# STM32H730_PINOUT.net
KiCad netlist of a schematic drawn in Altium Designer
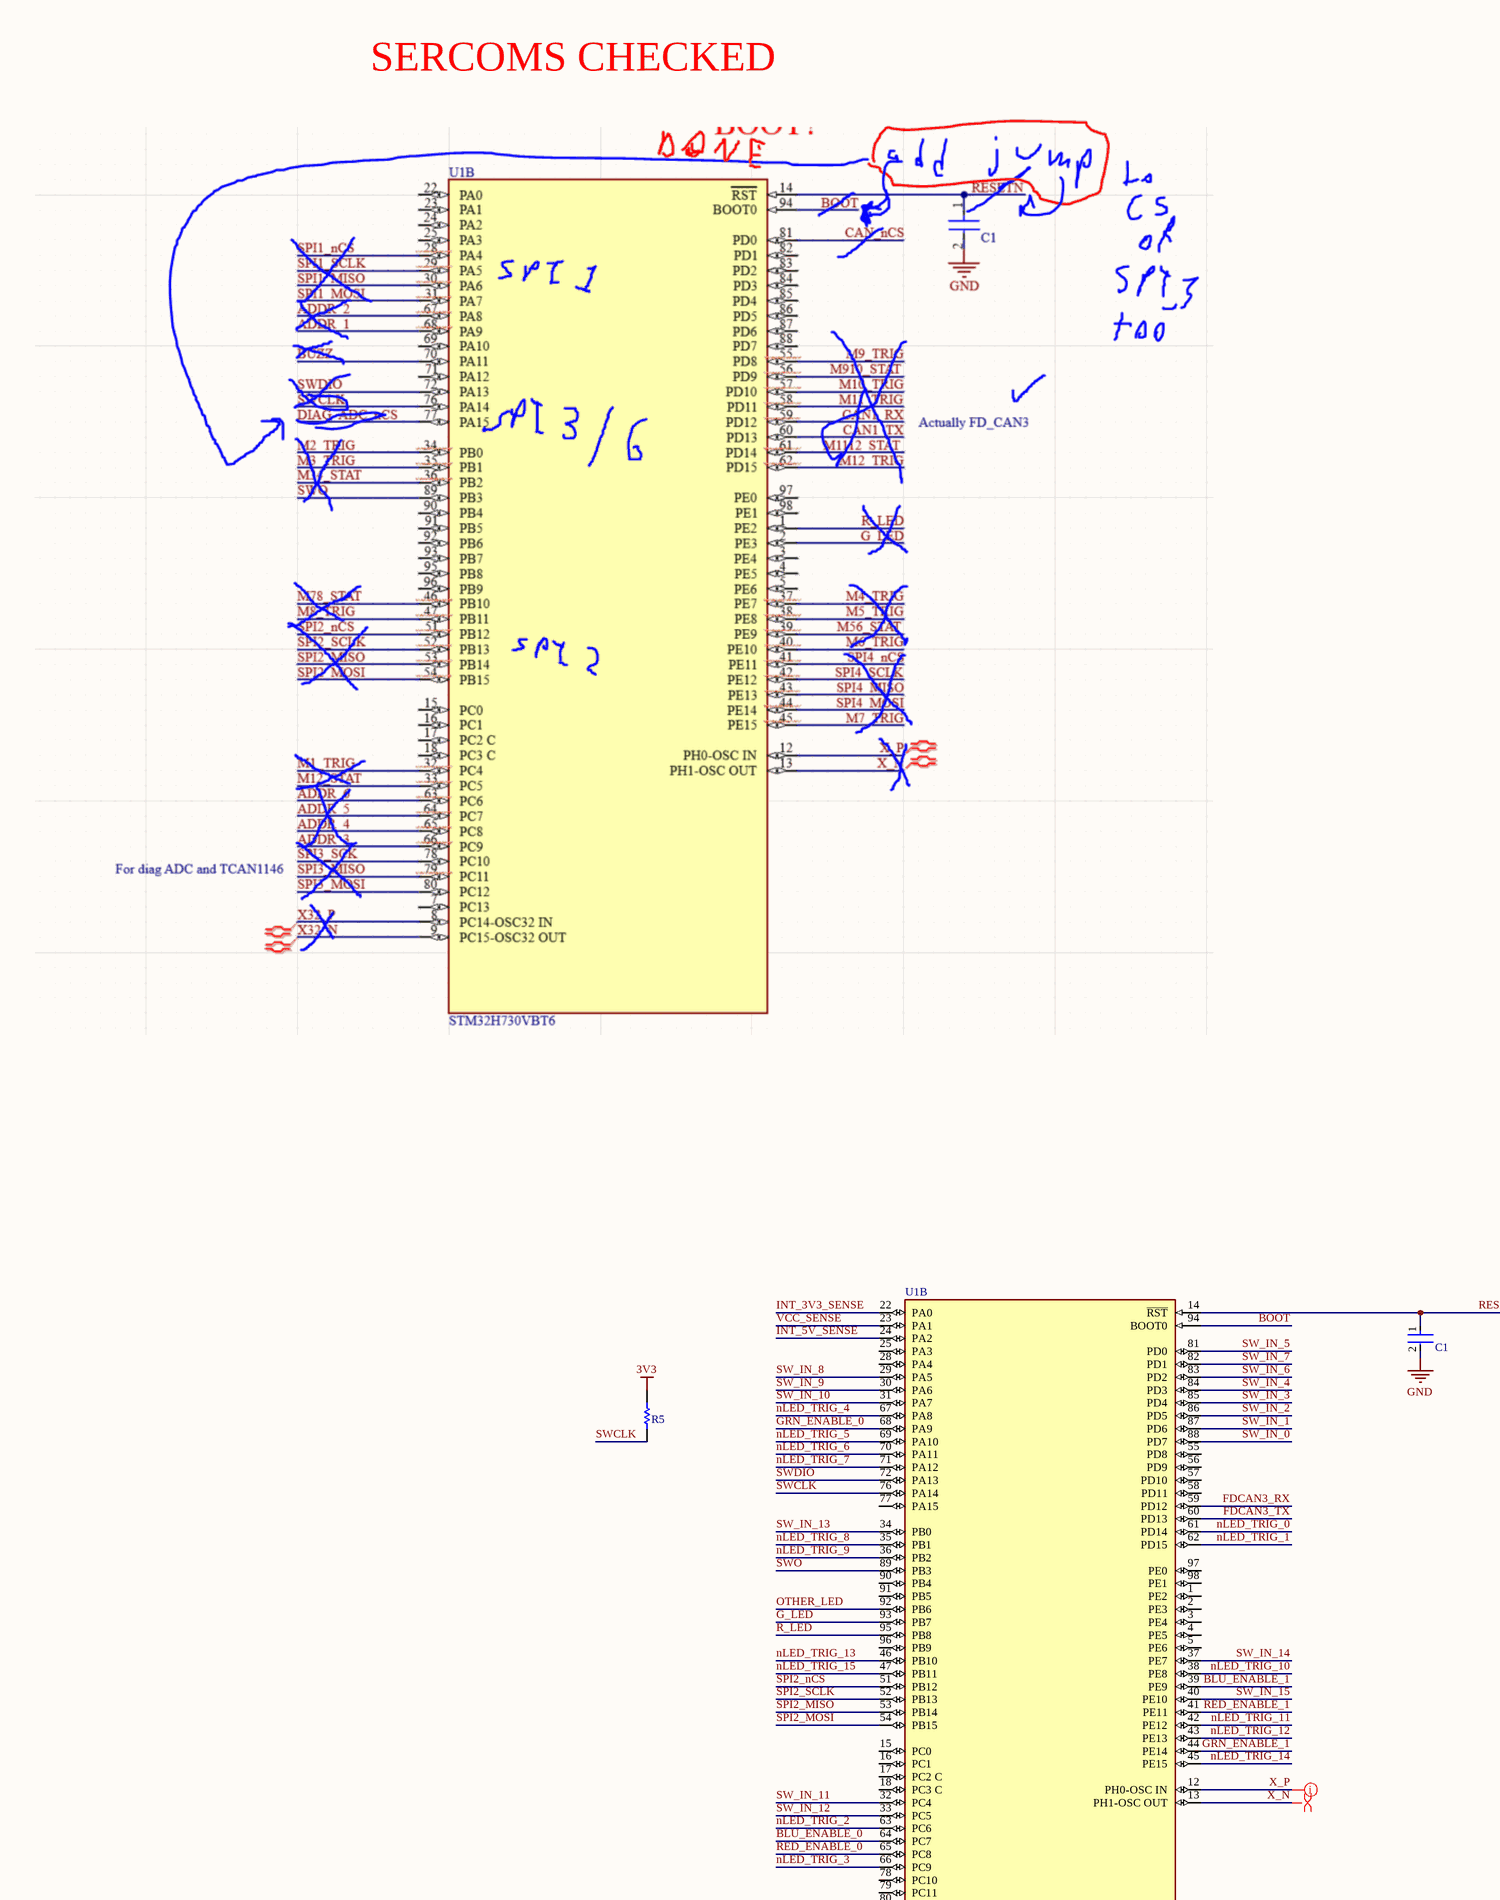
[diagram p0: STM32H730_PINOUT.SchDoc, top left]
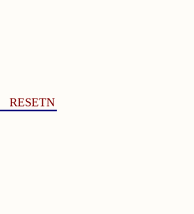
[diagram p1: STM32H730_PINOUT.SchDoc, top middle]
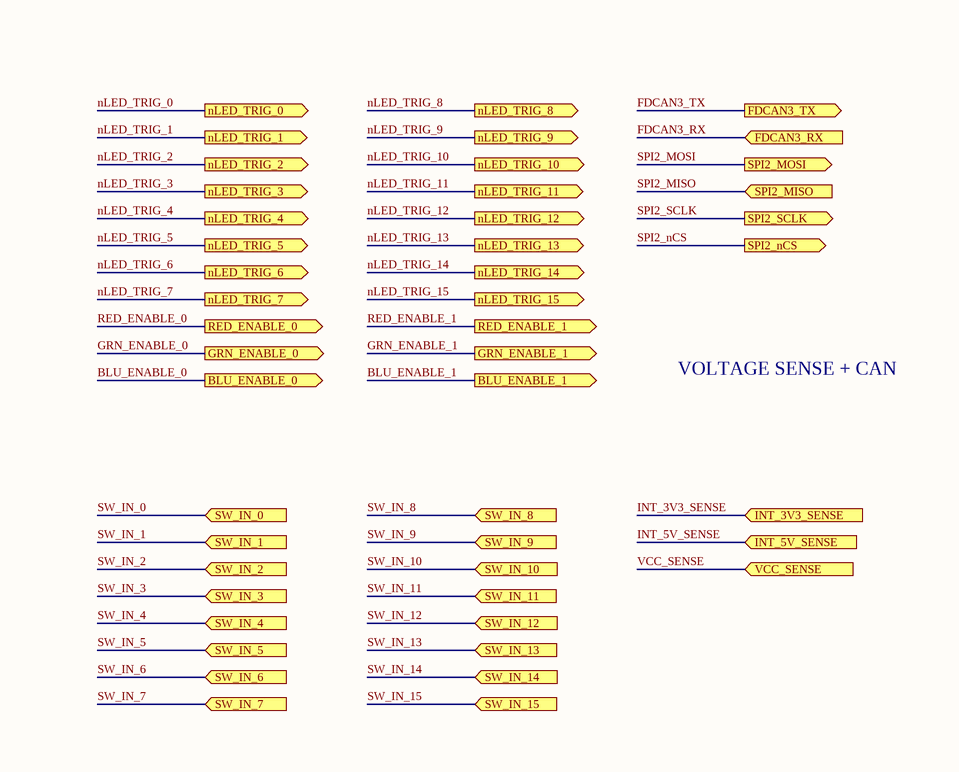
[diagram p2: STM32H730_PINOUT.SchDoc, top right]
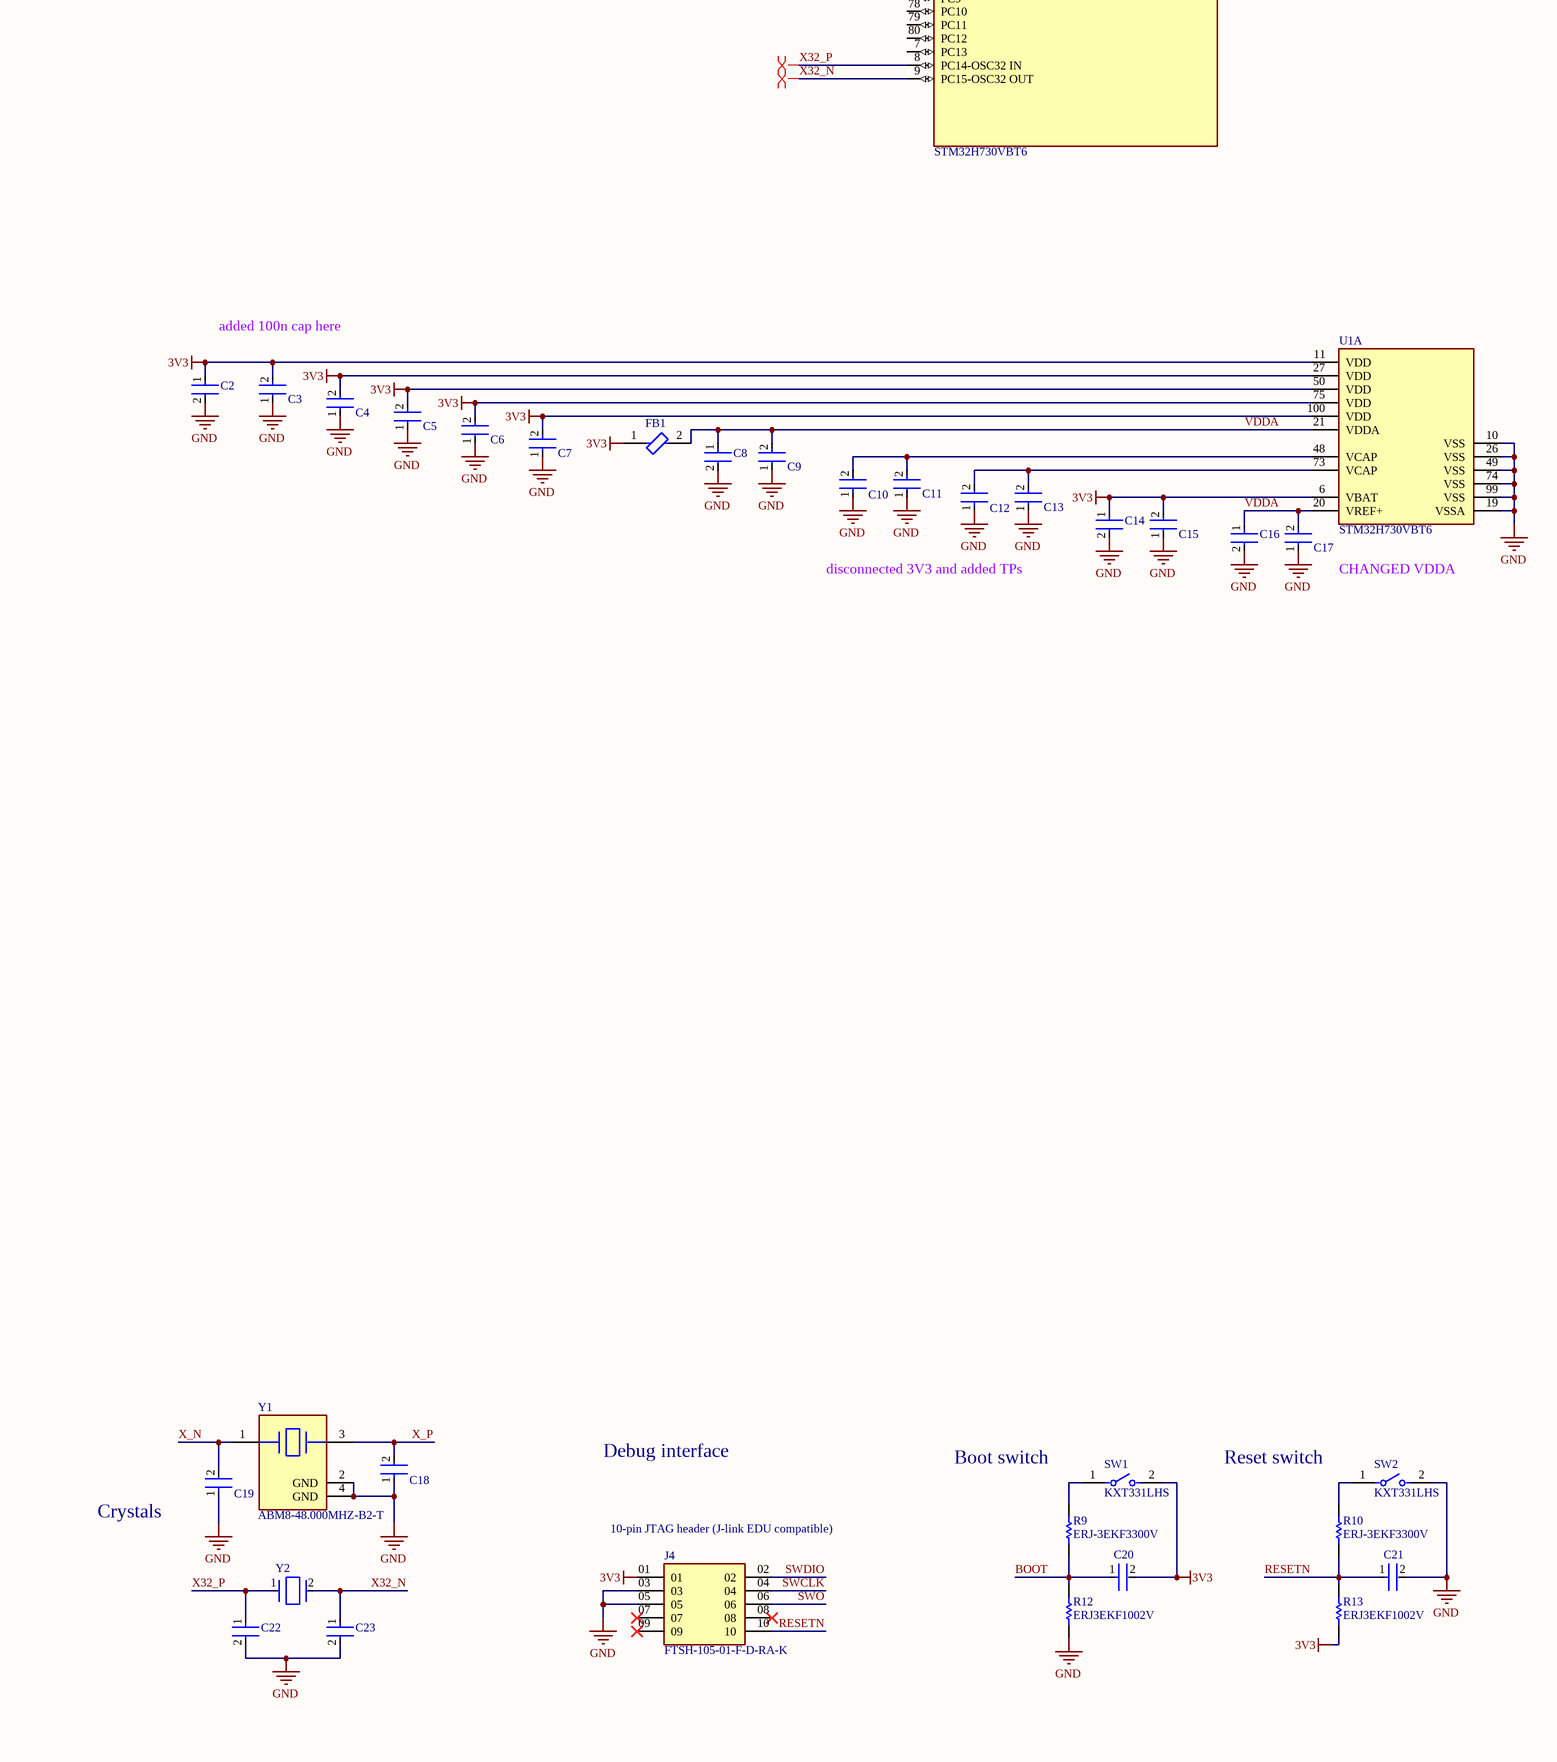
[diagram p3: STM32H730_PINOUT.SchDoc, bottom left]
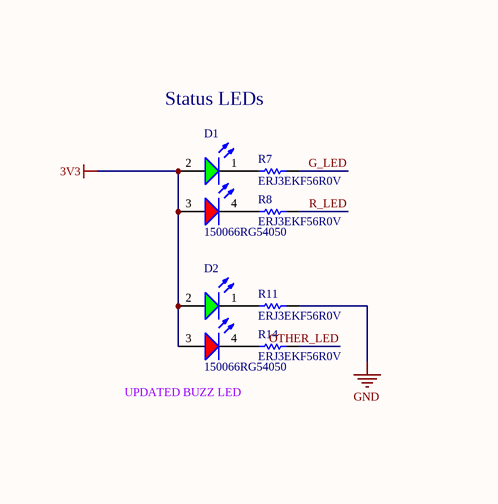
[diagram p4: STM32H730_PINOUT.SchDoc, bottom middle]
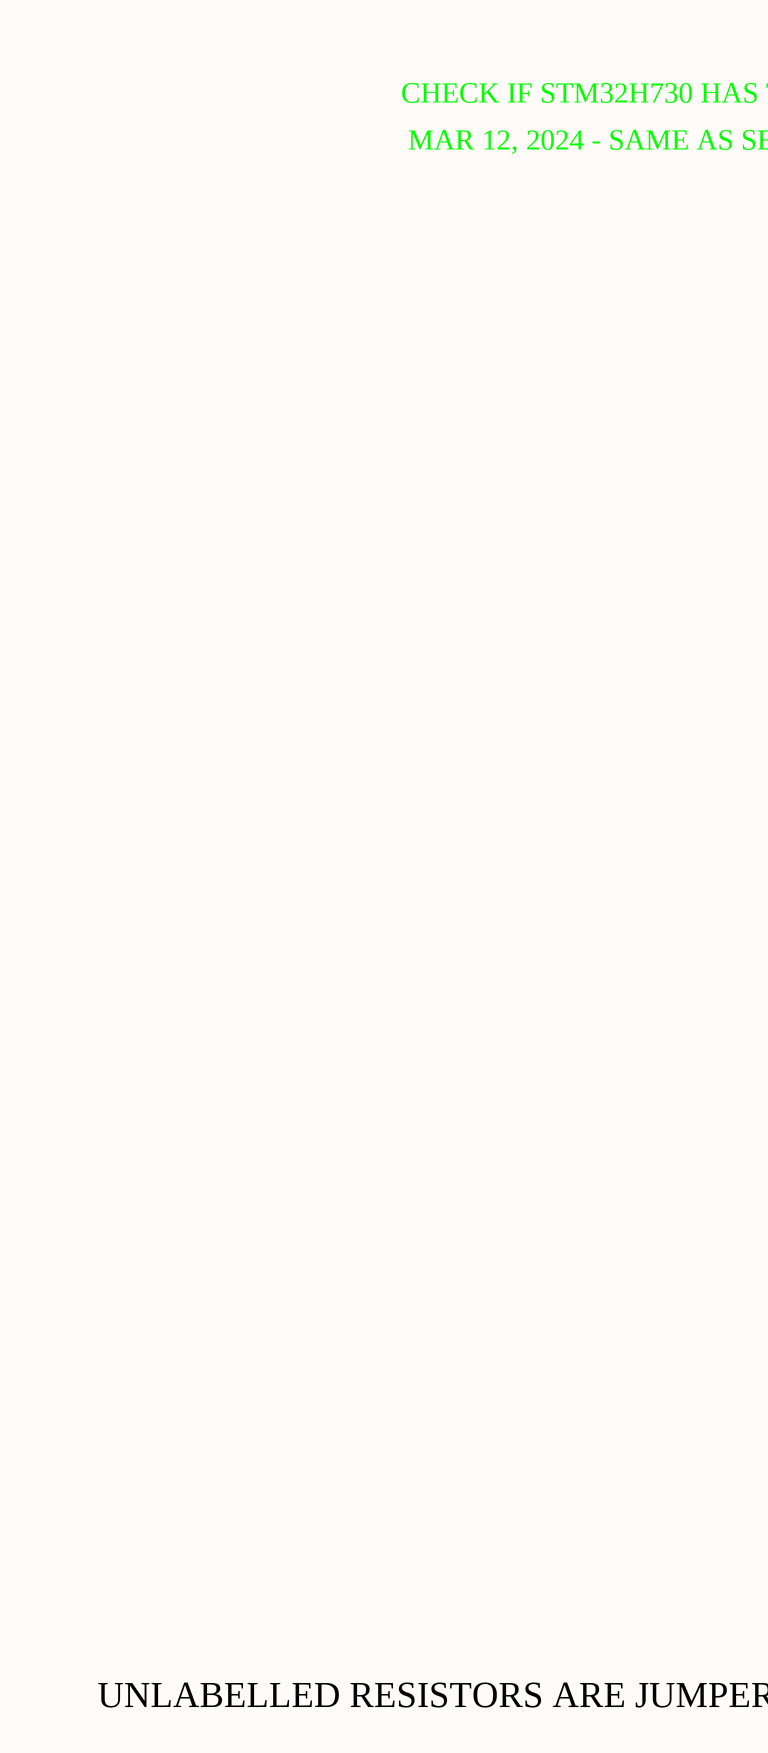
[diagram p5: STM32H730_PINOUT.SchDoc, bottom right]

(export (version "E")
  (design (tool "Eeschema 10.0.6"))
  (components
    (comp (ref "C1")
      (value "C0402C104K8PACTU")
      (footprint "FP-C0402-BB-MFG")
      (description "CAP CER 0.1UF 10V X5R 0402")
      (fields (field (name "MANUFACTURER") "Kemet") (field (name "TOLERANCE") "0.1"))
      (libsource (lib "Altium Content Vault") (part "b4654b650e69147ec39a6b967a45e02"))
    )
    (comp (ref "C2")
      (value "C1005X5R1A475K050BC")
      (footprint "FP-C1005-050-0_15-MFG")
      (description "CAP CER 4.7UF 10V X5R 0402")
      (fields (field (name "TOLERANCE") "10%"))
      (libsource (lib "Altium Content Vault") (part "b4654b650e69147ec39a6b967a45e02"))
    )
    (comp (ref "C3")
      (value "GRM155R71C104KA88D")
      (footprint "FP-GRM15-MFG")
      (description "CAP CER 0.1UF 16V X7R 0402")
      (fields
        (field (name "TOLERANCE") "10%")
        (field (name "OCTOPART") "https://octopart.com/grm155r71c104ka88d-murata-196880")
      )
      (libsource (lib "Altium Content Vault") (part "236180d848d6139a670b325ea6854c9"))
    )
    (comp (ref "C4")
      (value "GRM155R71C104KA88D")
      (footprint "FP-GRM15-MFG")
      (description "CAP CER 0.1UF 16V X7R 0402")
      (fields
        (field (name "TOLERANCE") "10%")
        (field (name "OCTOPART") "https://octopart.com/grm155r71c104ka88d-murata-196880")
      )
      (libsource (lib "Altium Content Vault") (part "236180d848d6139a670b325ea6854c9"))
    )
    (comp (ref "C5")
      (value "GRM155R71C104KA88D")
      (footprint "FP-GRM15-MFG")
      (description "CAP CER 0.1UF 16V X7R 0402")
      (fields
        (field (name "TOLERANCE") "10%")
        (field (name "OCTOPART") "https://octopart.com/grm155r71c104ka88d-murata-196880")
      )
      (libsource (lib "Altium Content Vault") (part "236180d848d6139a670b325ea6854c9"))
    )
    (comp (ref "C6")
      (value "GRM155R71C104KA88D")
      (footprint "FP-GRM15-MFG")
      (description "CAP CER 0.1UF 16V X7R 0402")
      (fields
        (field (name "TOLERANCE") "10%")
        (field (name "OCTOPART") "https://octopart.com/grm155r71c104ka88d-murata-196880")
      )
      (libsource (lib "Altium Content Vault") (part "236180d848d6139a670b325ea6854c9"))
    )
    (comp (ref "C7")
      (value "GRM155R71C104KA88D")
      (footprint "FP-GRM15-MFG")
      (description "CAP CER 0.1UF 16V X7R 0402")
      (fields
        (field (name "TOLERANCE") "10%")
        (field (name "OCTOPART") "https://octopart.com/grm155r71c104ka88d-murata-196880")
      )
      (libsource (lib "Altium Content Vault") (part "236180d848d6139a670b325ea6854c9"))
    )
    (comp (ref "C8")
      (value "EMK105BJ105KV-F")
      (footprint "FP-0402-L_1_0_0_05-W_0_5-IPC_A")
      (description "None")
      (fields (field (name "TOLERANCE") "10%"))
      (libsource (lib "Altium Content Vault") (part "b4654b650e69147ec39a6b967a45e02"))
    )
    (comp (ref "C9")
      (value "GRM155R71C104KA88D")
      (footprint "FP-GRM15-MFG")
      (description "CAP CER 0.1UF 16V X7R 0402")
      (fields
        (field (name "TOLERANCE") "10%")
        (field (name "OCTOPART") "https://octopart.com/grm155r71c104ka88d-murata-196880")
      )
      (libsource (lib "Altium Content Vault") (part "236180d848d6139a670b325ea6854c9"))
    )
    (comp (ref "C10")
      (value "C1005X7S1A225K050BC")
      (footprint "FP-C1005-050-0_15-0_1-MFG")
      (description "CAP CER 2.2UF 10V X7S 0402")
      (fields (field (name "TOLERANCE") "10%"))
      (libsource (lib "Altium Content Vault") (part "b4654b650e69147ec39a6b967a45e02"))
    )
    (comp (ref "C11")
      (value "GRM155R71C104KA88D")
      (footprint "FP-GRM15-MFG")
      (description "CAP CER 0.1UF 16V X7R 0402")
      (fields
        (field (name "TOLERANCE") "10%")
        (field (name "OCTOPART") "https://octopart.com/grm155r71c104ka88d-murata-196880")
      )
      (libsource (lib "Altium Content Vault") (part "236180d848d6139a670b325ea6854c9"))
    )
    (comp (ref "C12")
      (value "C1005X7S1A225K050BC")
      (footprint "FP-C1005-050-0_15-0_1-MFG")
      (description "CAP CER 2.2UF 10V X7S 0402")
      (fields (field (name "TOLERANCE") "10%"))
      (libsource (lib "Altium Content Vault") (part "b4654b650e69147ec39a6b967a45e02"))
    )
    (comp (ref "C13")
      (value "GRM155R71C104KA88D")
      (footprint "FP-GRM15-MFG")
      (description "CAP CER 0.1UF 16V X7R 0402")
      (fields
        (field (name "TOLERANCE") "10%")
        (field (name "OCTOPART") "https://octopart.com/grm155r71c104ka88d-murata-196880")
      )
      (libsource (lib "Altium Content Vault") (part "236180d848d6139a670b325ea6854c9"))
    )
    (comp (ref "C14")
      (value "EMK105BJ105KV-F")
      (footprint "FP-0402-L_1_0_0_05-W_0_5-IPC_A")
      (description "None")
      (fields (field (name "TOLERANCE") "10%"))
      (libsource (lib "Altium Content Vault") (part "b4654b650e69147ec39a6b967a45e02"))
    )
    (comp (ref "C15")
      (value "GRM155R71C104KA88D")
      (footprint "FP-GRM15-MFG")
      (description "CAP CER 0.1UF 16V X7R 0402")
      (fields
        (field (name "TOLERANCE") "10%")
        (field (name "OCTOPART") "https://octopart.com/grm155r71c104ka88d-murata-196880")
      )
      (libsource (lib "Altium Content Vault") (part "236180d848d6139a670b325ea6854c9"))
    )
    (comp (ref "C16")
      (value "EMK105BJ105KV-F")
      (footprint "FP-0402-L_1_0_0_05-W_0_5-IPC_A")
      (description "None")
      (fields (field (name "TOLERANCE") "10%"))
      (libsource (lib "Altium Content Vault") (part "b4654b650e69147ec39a6b967a45e02"))
    )
    (comp (ref "C17")
      (value "GRM155R71C104KA88D")
      (footprint "FP-GRM15-MFG")
      (description "CAP CER 0.1UF 16V X7R 0402")
      (fields
        (field (name "TOLERANCE") "10%")
        (field (name "OCTOPART") "https://octopart.com/grm155r71c104ka88d-murata-196880")
      )
      (libsource (lib "Altium Content Vault") (part "236180d848d6139a670b325ea6854c9"))
    )
    (comp (ref "C18")
      (value "08051A6R8CAT2A")
      (footprint "FP-0805-L_2_01_0_2-W_1_25-MFG")
      (description "General Purpose Ceramic Capacitor, 0805, 6.8pF, 0.25pF, C0G, 30ppm/°C, 100V")
      (fields (field (name "VOLTAGE") "100V") (field (name "TOLERANCE") "5%"))
      (libsource (lib "Altium Content Vault") (part "02cd4be3c70576c341d710602a673aa"))
    )
    (comp (ref "C19")
      (value "08051A6R8CAT2A")
      (footprint "FP-0805-L_2_01_0_2-W_1_25-MFG")
      (description "General Purpose Ceramic Capacitor, 0805, 6.8pF, 0.25pF, C0G, 30ppm/°C, 100V")
      (fields (field (name "VOLTAGE") "100V") (field (name "TOLERANCE") "5%"))
      (libsource (lib "Altium Content Vault") (part "02cd4be3c70576c341d710602a673aa"))
    )
    (comp (ref "C20")
      (value "C0402C104K8PACTU")
      (footprint "FP-C0402-BB-MFG")
      (description "CAP CER 0.1UF 10V X5R 0402")
      (fields (field (name "MANUFACTURER") "Kemet") (field (name "TOLERANCE") "0.1"))
      (libsource (lib "Altium Content Vault") (part "b4654b650e69147ec39a6b967a45e02"))
    )
    (comp (ref "C21")
      (value "C0402C104K8PACTU")
      (footprint "FP-C0402-BB-MFG")
      (description "CAP CER 0.1UF 10V X5R 0402")
      (fields (field (name "MANUFACTURER") "Kemet") (field (name "TOLERANCE") "0.1"))
      (libsource (lib "Altium Content Vault") (part "b4654b650e69147ec39a6b967a45e02"))
    )
    (comp (ref "C22")
      (value "04025A180FAT2A")
      (footprint "FP-0402-L_1_0_1-W_0_5_0_1-IPC_A")
      (description "General Purpose Ceramic Capacitor, 0402, 18pF, 1%, C0G, 30ppm/°C, 50V")
      (fields (field (name "TOLERANCE") "1%"))
      (libsource (lib "Altium Content Vault") (part "b4654b650e69147ec39a6b967a45e02"))
    )
    (comp (ref "C23")
      (value "04025A180FAT2A")
      (footprint "FP-0402-L_1_0_1-W_0_5_0_1-IPC_A")
      (description "General Purpose Ceramic Capacitor, 0402, 18pF, 1%, C0G, 30ppm/°C, 50V")
      (fields (field (name "TOLERANCE") "1%"))
      (libsource (lib "Altium Content Vault") (part "b4654b650e69147ec39a6b967a45e02"))
    )
    (comp (ref "D1")
      (value "150066RG54050")
      (footprint "WL-SBCD_0606")
      (description "Led, Red/Grn, 180Mcd/230Mcd, 624Nm/525Nm Rohs Compliant: Yes")
      (fields (field (name "SOURCE") "rgled.SchLib"))
      (libsource (lib "Space Concordia") (part "CMP-004-00034-2"))
    )
    (comp (ref "D2")
      (value "150066RG54050")
      (footprint "WL-SBCD_0606")
      (description "Led, Red/Grn, 180Mcd/230Mcd, 624Nm/525Nm Rohs Compliant: Yes")
      (fields (field (name "SOURCE") "rgled.SchLib"))
      (libsource (lib "Space Concordia") (part "CMP-004-00034-2"))
    )
    (comp (ref "FB1")
      (value "BLM15PX601SN1D")
      (footprint "FP-BLM15-0_05-MFG")
      (description "Chip Ferrite Bead, 0402, 600Ω @ 100MHz, 0.23Ω, 25%, 900mA")
      (fields (field (name "TOLERANCE") "25%"))
      (libsource (lib "Altium Content Vault") (part "5f30dd21d616792df468990f7003faa"))
    )
    (comp (ref "J4")
      (value "FTSH-105-01-F-D-RA-K")
      (footprint "FTSH-105-01-F-D-RA-K-Footprint-1")
      (libsource (lib "Space Concordia") (part "FTSH-105-01-F-D-RA-K-Symbol-1"))
    )
    (comp (ref "R5")
      (value "ERJ3EKF1002V")
      (footprint "RESC1609X55X30LL15T15")
      (description "Chip Resistor, 10 KOhm, +/- 1%, 0.1 W, -55 to 155 degC, 0603 (1608 Metric), RoHS, Tape and Reel")
      (fields (field (name "TOLERANCE") "1%") (field (name "MANUFACTURER") "Panasonic"))
      (libsource (lib "Altium Content Vault") (part "RES-2"))
    )
    (comp (ref "R7")
      (value "ERJ3EKF56R0V")
      (footprint "RESC1608X55X30NL15T15")
      (fields (field (name "MANUFACTURER") "Panasonic"))
      (libsource (lib "Altium Content Vault") (part "RES"))
    )
    (comp (ref "R8")
      (value "ERJ3EKF56R0V")
      (footprint "RESC1608X55X30NL15T15")
      (fields (field (name "MANUFACTURER") "Panasonic"))
      (libsource (lib "Altium Content Vault") (part "RES"))
    )
    (comp (ref "R9")
      (value "ERJ-3EKF3300V")
      (footprint "RESC1608X55X30LL15T15")
      (description "Chip Resistor, 330 Ohm, +/- 1%, 0.1 W, -55 to 155 degC, 0603 (1608 Metric), RoHS, Tape and Reel")
      (libsource (lib "Altium Content Vault") (part "RES-2"))
    )
    (comp (ref "R10")
      (value "ERJ-3EKF3300V")
      (footprint "RESC1608X55X30LL15T15")
      (description "Chip Resistor, 330 Ohm, +/- 1%, 0.1 W, -55 to 155 degC, 0603 (1608 Metric), RoHS, Tape and Reel")
      (libsource (lib "Altium Content Vault") (part "RES-2"))
    )
    (comp (ref "R11")
      (value "ERJ3EKF56R0V")
      (footprint "RESC1608X55X30NL15T15")
      (fields (field (name "MANUFACTURER") "Panasonic"))
      (libsource (lib "Altium Content Vault") (part "RES"))
    )
    (comp (ref "R12")
      (value "ERJ3EKF1002V")
      (footprint "RESC1609X55X30LL15T15")
      (description "Chip Resistor, 10 KOhm, +/- 1%, 0.1 W, -55 to 155 degC, 0603 (1608 Metric), RoHS, Tape and Reel")
      (fields (field (name "TOLERANCE") "1%") (field (name "MANUFACTURER") "Panasonic"))
      (libsource (lib "Altium Content Vault") (part "RES-2"))
    )
    (comp (ref "R13")
      (value "ERJ3EKF1002V")
      (footprint "RESC1609X55X30LL15T15")
      (description "Chip Resistor, 10 KOhm, +/- 1%, 0.1 W, -55 to 155 degC, 0603 (1608 Metric), RoHS, Tape and Reel")
      (fields (field (name "TOLERANCE") "1%") (field (name "MANUFACTURER") "Panasonic"))
      (libsource (lib "Altium Content Vault") (part "RES-2"))
    )
    (comp (ref "R14")
      (value "ERJ3EKF56R0V")
      (footprint "RESC1608X55X30NL15T15")
      (fields (field (name "MANUFACTURER") "Panasonic"))
      (libsource (lib "Altium Content Vault") (part "RES"))
    )
    (comp (ref "SW1")
      (value "KXT331LHS")
      (footprint "FP-KXT331LHS-MFG")
      (description "SWITCH TACTILE SPST-NO 0.02A 15V")
      (libsource (lib "Altium Content Vault") (part "bb27bde45df87f1f469753f287ef5ae"))
    )
    (comp (ref "SW2")
      (value "KXT331LHS")
      (footprint "FP-KXT331LHS-MFG")
      (description "SWITCH TACTILE SPST-NO 0.02A 15V")
      (libsource (lib "Altium Content Vault") (part "bb27bde45df87f1f469753f287ef5ae"))
    )
    (comp (ref "U1")
      (value "STM32H730VBT6")
      (footprint "FP-LQFP100-1L-IPC_C")
      (description "IC MCU 32BIT 128KB FLASH 100LQFP")
      (libsource (lib "Altium Content Vault") (part "44dc6501260a4d92b846760feb66c20"))
    )
    (comp (ref "Y1")
      (value "ABM8-48.000MHZ-B2-T")
      (footprint "FP-ABM8-MFG")
      (description "Crystal 48MHz ±20ppm 18pF SMD-4 3.2mm x 2.5mm")
      (fields (field (name "TOLERANCE") "20ppm"))
      (libsource (lib "Altium Content Vault") (part "dfdb7f9a12507849fb681da9a70121c"))
    )
    (comp (ref "Y2")
      (value "ECS-.327-12.5-1210-TR")
      (footprint "FP-ECX-1210-MFG")
      (description "CRYSTAL 32.7680KHZ 12.5PF SMD")
      (fields
        (field (name "OCTOPART") "https://octopart.com/ecs-.327-12.5-1210-tr-ecs+international-81221340")
        (field (name "TOLERANCE") "20ppm")
      )
      (libsource (lib "Altium Content Vault") (part "99724985039315a44fd0d1401b84e49"))
    )
  )
  (nets
    (net (code "1") (name "/BLU_ENABLE_0") (class "Default")
      (node (ref "U1") (pin "64") (pinfunction "PC7_64") (pintype "bidirectional"))
    )
    (net (code "2") (name "/BLU_ENABLE_1") (class "Default")
      (node (ref "U1") (pin "39") (pinfunction "PE9_39") (pintype "bidirectional"))
    )
    (net (code "3") (name "/BOOT") (class "Default")
      (node (ref "C20") (pin "1") (pinfunction "1_1") (pintype "passive"))
      (node (ref "R12") (pin "2") (pinfunction "2_2") (pintype "passive"))
      (node (ref "R9") (pin "1") (pinfunction "1_1") (pintype "passive"))
      (node (ref "U1") (pin "94") (pinfunction "BOOT0_94") (pintype "input"))
    )
    (net (code "4") (name "/FDCAN3_RX") (class "Default")
      (node (ref "U1") (pin "59") (pinfunction "PD12_59") (pintype "bidirectional"))
    )
    (net (code "5") (name "/FDCAN3_TX") (class "Default")
      (node (ref "U1") (pin "60") (pinfunction "PD13_60") (pintype "bidirectional"))
    )
    (net (code "6") (name "/GRN_ENABLE_0") (class "Default")
      (node (ref "U1") (pin "68") (pinfunction "PA9_68") (pintype "bidirectional"))
    )
    (net (code "7") (name "/GRN_ENABLE_1") (class "Default")
      (node (ref "U1") (pin "44") (pinfunction "PE14_44") (pintype "bidirectional"))
    )
    (net (code "8") (name "/G_LED") (class "Default")
      (node (ref "R7") (pin "1") (pinfunction "1_1") (pintype "passive"))
      (node (ref "U1") (pin "93") (pinfunction "PB7_93") (pintype "bidirectional"))
    )
    (net (code "9") (name "/INT_3V3_SENSE") (class "Default")
      (node (ref "U1") (pin "22") (pinfunction "PA0_22") (pintype "bidirectional"))
    )
    (net (code "10") (name "/INT_5V_SENSE") (class "Default")
      (node (ref "U1") (pin "24") (pinfunction "PA2_24") (pintype "bidirectional"))
    )
    (net (code "11") (name "/OTHER_LED") (class "Default")
      (node (ref "R14") (pin "1") (pinfunction "1_1") (pintype "passive"))
      (node (ref "U1") (pin "92") (pinfunction "PB6_92") (pintype "bidirectional"))
    )
    (net (code "12") (name "/RED_ENABLE_0") (class "Default")
      (node (ref "U1") (pin "65") (pinfunction "PC8_65") (pintype "bidirectional"))
    )
    (net (code "13") (name "/RED_ENABLE_1") (class "Default")
      (node (ref "U1") (pin "41") (pinfunction "PE11_41") (pintype "bidirectional"))
    )
    (net (code "14") (name "/RESETN") (class "Default")
      (node (ref "C1") (pin "1") (pinfunction "1_1") (pintype "passive"))
      (node (ref "C21") (pin "1") (pinfunction "1_1") (pintype "passive"))
      (node (ref "J4") (pin "10") (pinfunction "10_10") (pintype "passive"))
      (node (ref "R10") (pin "1") (pinfunction "1_1") (pintype "passive"))
      (node (ref "R13") (pin "2") (pinfunction "2_2") (pintype "passive"))
      (node (ref "U1") (pin "14") (pinfunction "~{RST}_14") (pintype "input"))
    )
    (net (code "15") (name "/R_LED") (class "Default")
      (node (ref "R8") (pin "1") (pinfunction "1_1") (pintype "passive"))
      (node (ref "U1") (pin "95") (pinfunction "PB8_95") (pintype "bidirectional"))
    )
    (net (code "16") (name "/SPI2_MISO") (class "Default")
      (node (ref "U1") (pin "53") (pinfunction "PB14_53") (pintype "bidirectional"))
    )
    (net (code "17") (name "/SPI2_MOSI") (class "Default")
      (node (ref "U1") (pin "54") (pinfunction "PB15_54") (pintype "bidirectional"))
    )
    (net (code "18") (name "/SPI2_SCLK") (class "Default")
      (node (ref "U1") (pin "52") (pinfunction "PB13_52") (pintype "bidirectional"))
    )
    (net (code "19") (name "/SPI2_nCS") (class "Default")
      (node (ref "U1") (pin "51") (pinfunction "PB12_51") (pintype "bidirectional"))
    )
    (net (code "20") (name "/SWCLK") (class "Default")
      (node (ref "J4") (pin "04") (pinfunction "04_04") (pintype "passive"))
      (node (ref "R5") (pin "2") (pinfunction "2_2") (pintype "passive"))
      (node (ref "U1") (pin "76") (pinfunction "PA14_76") (pintype "bidirectional"))
    )
    (net (code "21") (name "/SWDIO") (class "Default")
      (node (ref "J4") (pin "02") (pinfunction "02_02") (pintype "passive"))
      (node (ref "U1") (pin "72") (pinfunction "PA13_72") (pintype "bidirectional"))
    )
    (net (code "22") (name "/SWO") (class "Default")
      (node (ref "J4") (pin "06") (pinfunction "06_06") (pintype "passive"))
      (node (ref "U1") (pin "89") (pinfunction "PB3_89") (pintype "bidirectional"))
    )
    (net (code "23") (name "/SW_IN_0") (class "Default")
      (node (ref "U1") (pin "88") (pinfunction "PD7_88") (pintype "bidirectional"))
    )
    (net (code "24") (name "/SW_IN_1") (class "Default")
      (node (ref "U1") (pin "87") (pinfunction "PD6_87") (pintype "bidirectional"))
    )
    (net (code "25") (name "/SW_IN_2") (class "Default")
      (node (ref "U1") (pin "86") (pinfunction "PD5_86") (pintype "bidirectional"))
    )
    (net (code "26") (name "/SW_IN_3") (class "Default")
      (node (ref "U1") (pin "85") (pinfunction "PD4_85") (pintype "bidirectional"))
    )
    (net (code "27") (name "/SW_IN_4") (class "Default")
      (node (ref "U1") (pin "84") (pinfunction "PD3_84") (pintype "bidirectional"))
    )
    (net (code "28") (name "/SW_IN_5") (class "Default")
      (node (ref "U1") (pin "81") (pinfunction "PD0_81") (pintype "bidirectional"))
    )
    (net (code "29") (name "/SW_IN_6") (class "Default")
      (node (ref "U1") (pin "83") (pinfunction "PD2_83") (pintype "bidirectional"))
    )
    (net (code "30") (name "/SW_IN_7") (class "Default")
      (node (ref "U1") (pin "82") (pinfunction "PD1_82") (pintype "bidirectional"))
    )
    (net (code "31") (name "/SW_IN_8") (class "Default")
      (node (ref "U1") (pin "29") (pinfunction "PA5_29") (pintype "bidirectional"))
    )
    (net (code "32") (name "/SW_IN_9") (class "Default")
      (node (ref "U1") (pin "30") (pinfunction "PA6_30") (pintype "bidirectional"))
    )
    (net (code "33") (name "/SW_IN_10") (class "Default")
      (node (ref "U1") (pin "31") (pinfunction "PA7_31") (pintype "bidirectional"))
    )
    (net (code "34") (name "/SW_IN_11") (class "Default")
      (node (ref "U1") (pin "32") (pinfunction "PC4_32") (pintype "bidirectional"))
    )
    (net (code "35") (name "/SW_IN_12") (class "Default")
      (node (ref "U1") (pin "33") (pinfunction "PC5_33") (pintype "bidirectional"))
    )
    (net (code "36") (name "/SW_IN_13") (class "Default")
      (node (ref "U1") (pin "34") (pinfunction "PB0_34") (pintype "bidirectional"))
    )
    (net (code "37") (name "/SW_IN_14") (class "Default")
      (node (ref "U1") (pin "37") (pinfunction "PE7_37") (pintype "bidirectional"))
    )
    (net (code "38") (name "/SW_IN_15") (class "Default")
      (node (ref "U1") (pin "40") (pinfunction "PE10_40") (pintype "bidirectional"))
    )
    (net (code "39") (name "/VCC_SENSE") (class "Default")
      (node (ref "U1") (pin "23") (pinfunction "PA1_23") (pintype "bidirectional"))
    )
    (net (code "40") (name "/VDDA") (class "Default")
      (node (ref "C16") (pin "1") (pinfunction "1_1") (pintype "passive"))
      (node (ref "C17") (pin "2") (pinfunction "2_2") (pintype "passive"))
      (node (ref "C8") (pin "1") (pinfunction "1_1") (pintype "passive"))
      (node (ref "C9") (pin "2") (pinfunction "2_2") (pintype "passive"))
      (node (ref "FB1") (pin "2") (pinfunction "2_2") (pintype "passive"))
      (node (ref "U1") (pin "20") (pinfunction "VREF+_20") (pintype "power_in"))
      (node (ref "U1") (pin "21") (pinfunction "VDDA_21") (pintype "power_in"))
    )
    (net (code "41") (name "/X32_N") (class "Default")
      (node (ref "C23") (pin "1") (pinfunction "1_1") (pintype "passive"))
      (node (ref "U1") (pin "9") (pinfunction "PC15-OSC32_OUT_9") (pintype "bidirectional"))
      (node (ref "Y2") (pin "2") (pinfunction "Out/In_2") (pintype "passive"))
    )
    (net (code "42") (name "/X32_P") (class "Default")
      (node (ref "C22") (pin "1") (pinfunction "1_1") (pintype "passive"))
      (node (ref "U1") (pin "8") (pinfunction "PC14-OSC32_IN_8") (pintype "bidirectional"))
      (node (ref "Y2") (pin "1") (pinfunction "In/Out_1") (pintype "passive"))
    )
    (net (code "43") (name "/X_N") (class "Default")
      (node (ref "C19") (pin "2") (pinfunction "2_2") (pintype "passive"))
      (node (ref "U1") (pin "13") (pinfunction "PH1-OSC_OUT_13") (pintype "bidirectional"))
      (node (ref "Y1") (pin "1") (pinfunction "1_1") (pintype "passive"))
    )
    (net (code "44") (name "/X_P") (class "Default")
      (node (ref "C18") (pin "2") (pinfunction "2_2") (pintype "passive"))
      (node (ref "U1") (pin "12") (pinfunction "PH0-OSC_IN_12") (pintype "bidirectional"))
      (node (ref "Y1") (pin "3") (pinfunction "3_3") (pintype "passive"))
    )
    (net (code "45") (name "/nLED_TRIG_0") (class "Default")
      (node (ref "U1") (pin "61") (pinfunction "PD14_61") (pintype "bidirectional"))
    )
    (net (code "46") (name "/nLED_TRIG_1") (class "Default")
      (node (ref "U1") (pin "62") (pinfunction "PD15_62") (pintype "bidirectional"))
    )
    (net (code "47") (name "/nLED_TRIG_2") (class "Default")
      (node (ref "U1") (pin "63") (pinfunction "PC6_63") (pintype "bidirectional"))
    )
    (net (code "48") (name "/nLED_TRIG_3") (class "Default")
      (node (ref "U1") (pin "66") (pinfunction "PC9_66") (pintype "bidirectional"))
    )
    (net (code "49") (name "/nLED_TRIG_4") (class "Default")
      (node (ref "U1") (pin "67") (pinfunction "PA8_67") (pintype "bidirectional"))
    )
    (net (code "50") (name "/nLED_TRIG_5") (class "Default")
      (node (ref "U1") (pin "69") (pinfunction "PA10_69") (pintype "bidirectional"))
    )
    (net (code "51") (name "/nLED_TRIG_6") (class "Default")
      (node (ref "U1") (pin "70") (pinfunction "PA11_70") (pintype "bidirectional"))
    )
    (net (code "52") (name "/nLED_TRIG_7") (class "Default")
      (node (ref "U1") (pin "71") (pinfunction "PA12_71") (pintype "bidirectional"))
    )
    (net (code "53") (name "/nLED_TRIG_8") (class "Default")
      (node (ref "U1") (pin "35") (pinfunction "PB1_35") (pintype "bidirectional"))
    )
    (net (code "54") (name "/nLED_TRIG_9") (class "Default")
      (node (ref "U1") (pin "36") (pinfunction "PB2_36") (pintype "bidirectional"))
    )
    (net (code "55") (name "/nLED_TRIG_10") (class "Default")
      (node (ref "U1") (pin "38") (pinfunction "PE8_38") (pintype "bidirectional"))
    )
    (net (code "56") (name "/nLED_TRIG_11") (class "Default")
      (node (ref "U1") (pin "42") (pinfunction "PE12_42") (pintype "bidirectional"))
    )
    (net (code "57") (name "/nLED_TRIG_12") (class "Default")
      (node (ref "U1") (pin "43") (pinfunction "PE13_43") (pintype "bidirectional"))
    )
    (net (code "58") (name "/nLED_TRIG_13") (class "Default")
      (node (ref "U1") (pin "46") (pinfunction "PB10_46") (pintype "bidirectional"))
    )
    (net (code "59") (name "/nLED_TRIG_14") (class "Default")
      (node (ref "U1") (pin "45") (pinfunction "PE15_45") (pintype "bidirectional"))
    )
    (net (code "60") (name "/nLED_TRIG_15") (class "Default")
      (node (ref "U1") (pin "47") (pinfunction "PB11_47") (pintype "bidirectional"))
    )
    (net (code "61") (name "3V3") (class "Default")
      (node (ref "C14") (pin "1") (pinfunction "1_1") (pintype "passive"))
      (node (ref "C15") (pin "2") (pinfunction "2_2") (pintype "passive"))
      (node (ref "C2") (pin "1") (pinfunction "1_1") (pintype "passive"))
      (node (ref "C20") (pin "2") (pinfunction "2_2") (pintype "passive"))
      (node (ref "C3") (pin "2") (pinfunction "2_2") (pintype "passive"))
      (node (ref "C4") (pin "2") (pinfunction "2_2") (pintype "passive"))
      (node (ref "C5") (pin "2") (pinfunction "2_2") (pintype "passive"))
      (node (ref "C6") (pin "2") (pinfunction "2_2") (pintype "passive"))
      (node (ref "C7") (pin "2") (pinfunction "2_2") (pintype "passive"))
      (node (ref "D1") (pin "2") (pinfunction "A_2") (pintype "passive"))
      (node (ref "D1") (pin "3") (pinfunction "A_3") (pintype "passive"))
      (node (ref "D2") (pin "2") (pinfunction "A_2") (pintype "passive"))
      (node (ref "D2") (pin "3") (pinfunction "A_3") (pintype "passive"))
      (node (ref "FB1") (pin "1") (pinfunction "1_1") (pintype "passive"))
      (node (ref "J4") (pin "01") (pinfunction "01_01") (pintype "passive"))
      (node (ref "R13") (pin "1") (pinfunction "1_1") (pintype "passive"))
      (node (ref "R5") (pin "1") (pinfunction "1_1") (pintype "passive"))
      (node (ref "SW1") (pin "2") (pinfunction "2_2") (pintype "passive"))
      (node (ref "U1") (pin "100") (pinfunction "VDD_100") (pintype "power_in"))
      (node (ref "U1") (pin "11") (pinfunction "VDD_11") (pintype "power_in"))
      (node (ref "U1") (pin "27") (pinfunction "VDD_27") (pintype "power_in"))
      (node (ref "U1") (pin "50") (pinfunction "VDD_50") (pintype "power_in"))
      (node (ref "U1") (pin "6") (pinfunction "VBAT_6") (pintype "power_in"))
      (node (ref "U1") (pin "75") (pinfunction "VDD_75") (pintype "power_in"))
    )
    (net (code "62") (name "GND") (class "Default")
      (node (ref "C1") (pin "2") (pinfunction "2_2") (pintype "passive"))
      (node (ref "C10") (pin "1") (pinfunction "1_1") (pintype "passive"))
      (node (ref "C11") (pin "1") (pinfunction "1_1") (pintype "passive"))
      (node (ref "C12") (pin "1") (pinfunction "1_1") (pintype "passive"))
      (node (ref "C13") (pin "1") (pinfunction "1_1") (pintype "passive"))
      (node (ref "C14") (pin "2") (pinfunction "2_2") (pintype "passive"))
      (node (ref "C15") (pin "1") (pinfunction "1_1") (pintype "passive"))
      (node (ref "C16") (pin "2") (pinfunction "2_2") (pintype "passive"))
      (node (ref "C17") (pin "1") (pinfunction "1_1") (pintype "passive"))
      (node (ref "C18") (pin "1") (pinfunction "1_1") (pintype "passive"))
      (node (ref "C19") (pin "1") (pinfunction "1_1") (pintype "passive"))
      (node (ref "C2") (pin "2") (pinfunction "2_2") (pintype "passive"))
      (node (ref "C21") (pin "2") (pinfunction "2_2") (pintype "passive"))
      (node (ref "C22") (pin "2") (pinfunction "2_2") (pintype "passive"))
      (node (ref "C23") (pin "2") (pinfunction "2_2") (pintype "passive"))
      (node (ref "C3") (pin "1") (pinfunction "1_1") (pintype "passive"))
      (node (ref "C4") (pin "1") (pinfunction "1_1") (pintype "passive"))
      (node (ref "C5") (pin "1") (pinfunction "1_1") (pintype "passive"))
      (node (ref "C6") (pin "1") (pinfunction "1_1") (pintype "passive"))
      (node (ref "C7") (pin "1") (pinfunction "1_1") (pintype "passive"))
      (node (ref "C8") (pin "2") (pinfunction "2_2") (pintype "passive"))
      (node (ref "C9") (pin "1") (pinfunction "1_1") (pintype "passive"))
      (node (ref "J4") (pin "03") (pinfunction "03_03") (pintype "passive"))
      (node (ref "J4") (pin "05") (pinfunction "05_05") (pintype "passive"))
      (node (ref "R11") (pin "1") (pinfunction "1_1") (pintype "passive"))
      (node (ref "R12") (pin "1") (pinfunction "1_1") (pintype "passive"))
      (node (ref "SW2") (pin "2") (pinfunction "2_2") (pintype "passive"))
      (node (ref "U1") (pin "10") (pinfunction "VSS_10") (pintype "power_in"))
      (node (ref "U1") (pin "19") (pinfunction "VSSA_19") (pintype "power_in"))
      (node (ref "U1") (pin "26") (pinfunction "VSS_26") (pintype "power_in"))
      (node (ref "U1") (pin "49") (pinfunction "VSS_49") (pintype "power_in"))
      (node (ref "U1") (pin "74") (pinfunction "VSS_74") (pintype "power_in"))
      (node (ref "U1") (pin "99") (pinfunction "VSS_99") (pintype "power_in"))
      (node (ref "Y1") (pin "2") (pinfunction "GND_2") (pintype "power_in"))
      (node (ref "Y1") (pin "4") (pinfunction "GND_4") (pintype "power_in"))
    )
    (net (code "63") (name "Net-(C10-Pad2)") (class "Default")
      (node (ref "C10") (pin "2") (pinfunction "2_2") (pintype "passive"))
      (node (ref "C11") (pin "2") (pinfunction "2_2") (pintype "passive"))
      (node (ref "U1") (pin "48") (pinfunction "VCAP_48") (pintype "power_in"))
    )
    (net (code "64") (name "Net-(C12-Pad2)") (class "Default")
      (node (ref "C12") (pin "2") (pinfunction "2_2") (pintype "passive"))
      (node (ref "C13") (pin "2") (pinfunction "2_2") (pintype "passive"))
      (node (ref "U1") (pin "73") (pinfunction "VCAP_73") (pintype "power_in"))
    )
    (net (code "65") (name "Net-(D1-K-Pad1)") (class "Default")
      (node (ref "D1") (pin "1") (pinfunction "K_1") (pintype "passive"))
      (node (ref "R7") (pin "2") (pinfunction "2_2") (pintype "passive"))
    )
    (net (code "66") (name "Net-(D1-K-Pad4)") (class "Default")
      (node (ref "D1") (pin "4") (pinfunction "K_4") (pintype "passive"))
      (node (ref "R8") (pin "2") (pinfunction "2_2") (pintype "passive"))
    )
    (net (code "67") (name "Net-(D2-K-Pad1)") (class "Default")
      (node (ref "D2") (pin "1") (pinfunction "K_1") (pintype "passive"))
      (node (ref "R11") (pin "2") (pinfunction "2_2") (pintype "passive"))
    )
    (net (code "68") (name "Net-(D2-K-Pad4)") (class "Default")
      (node (ref "D2") (pin "4") (pinfunction "K_4") (pintype "passive"))
      (node (ref "R14") (pin "2") (pinfunction "2_2") (pintype "passive"))
    )
    (net (code "69") (name "Net-(R9-Pad2)") (class "Default")
      (node (ref "R9") (pin "2") (pinfunction "2_2") (pintype "passive"))
      (node (ref "SW1") (pin "1") (pinfunction "1_1") (pintype "passive"))
    )
    (net (code "70") (name "Net-(R10-Pad2)") (class "Default")
      (node (ref "R10") (pin "2") (pinfunction "2_2") (pintype "passive"))
      (node (ref "SW2") (pin "1") (pinfunction "1_1") (pintype "passive"))
    )
    (net (code "71") (name "unconnected-(J4-Pad07)") (class "Default")
      (node (ref "J4") (pin "07") (pinfunction "07_07") (pintype "passive+no_connect"))
    )
    (net (code "72") (name "unconnected-(J4-Pad08)") (class "Default")
      (node (ref "J4") (pin "08") (pinfunction "08_08") (pintype "passive+no_connect"))
    )
    (net (code "73") (name "unconnected-(J4-Pad09)") (class "Default")
      (node (ref "J4") (pin "09") (pinfunction "09_09") (pintype "passive+no_connect"))
    )
    (net (code "74") (name "unconnected-(U1B-PA3-Pad25)") (class "Default")
      (node (ref "U1") (pin "25") (pinfunction "PA3_25") (pintype "bidirectional"))
    )
    (net (code "75") (name "unconnected-(U1B-PA4-Pad28)") (class "Default")
      (node (ref "U1") (pin "28") (pinfunction "PA4_28") (pintype "bidirectional"))
    )
    (net (code "76") (name "unconnected-(U1B-PA15-Pad77)") (class "Default")
      (node (ref "U1") (pin "77") (pinfunction "PA15_77") (pintype "bidirectional"))
    )
    (net (code "77") (name "unconnected-(U1B-PB4-Pad90)") (class "Default")
      (node (ref "U1") (pin "90") (pinfunction "PB4_90") (pintype "bidirectional"))
    )
    (net (code "78") (name "unconnected-(U1B-PB5-Pad91)") (class "Default")
      (node (ref "U1") (pin "91") (pinfunction "PB5_91") (pintype "bidirectional"))
    )
    (net (code "79") (name "unconnected-(U1B-PB9-Pad96)") (class "Default")
      (node (ref "U1") (pin "96") (pinfunction "PB9_96") (pintype "bidirectional"))
    )
    (net (code "80") (name "unconnected-(U1B-PC0-Pad15)") (class "Default")
      (node (ref "U1") (pin "15") (pinfunction "PC0_15") (pintype "bidirectional"))
    )
    (net (code "81") (name "unconnected-(U1B-PC1-Pad16)") (class "Default")
      (node (ref "U1") (pin "16") (pinfunction "PC1_16") (pintype "bidirectional"))
    )
    (net (code "82") (name "unconnected-(U1B-PC2_C-Pad17)") (class "Default")
      (node (ref "U1") (pin "17") (pinfunction "PC2_C_17") (pintype "bidirectional"))
    )
    (net (code "83") (name "unconnected-(U1B-PC3_C-Pad18)") (class "Default")
      (node (ref "U1") (pin "18") (pinfunction "PC3_C_18") (pintype "bidirectional"))
    )
    (net (code "84") (name "unconnected-(U1B-PC10-Pad78)") (class "Default")
      (node (ref "U1") (pin "78") (pinfunction "PC10_78") (pintype "bidirectional"))
    )
    (net (code "85") (name "unconnected-(U1B-PC11-Pad79)") (class "Default")
      (node (ref "U1") (pin "79") (pinfunction "PC11_79") (pintype "bidirectional"))
    )
    (net (code "86") (name "unconnected-(U1B-PC12-Pad80)") (class "Default")
      (node (ref "U1") (pin "80") (pinfunction "PC12_80") (pintype "bidirectional"))
    )
    (net (code "87") (name "unconnected-(U1B-PC13-Pad7)") (class "Default")
      (node (ref "U1") (pin "7") (pinfunction "PC13_7") (pintype "bidirectional"))
    )
    (net (code "88") (name "unconnected-(U1B-PD8-Pad55)") (class "Default")
      (node (ref "U1") (pin "55") (pinfunction "PD8_55") (pintype "bidirectional"))
    )
    (net (code "89") (name "unconnected-(U1B-PD9-Pad56)") (class "Default")
      (node (ref "U1") (pin "56") (pinfunction "PD9_56") (pintype "bidirectional"))
    )
    (net (code "90") (name "unconnected-(U1B-PD10-Pad57)") (class "Default")
      (node (ref "U1") (pin "57") (pinfunction "PD10_57") (pintype "bidirectional"))
    )
    (net (code "91") (name "unconnected-(U1B-PD11-Pad58)") (class "Default")
      (node (ref "U1") (pin "58") (pinfunction "PD11_58") (pintype "bidirectional"))
    )
    (net (code "92") (name "unconnected-(U1B-PE0-Pad97)") (class "Default")
      (node (ref "U1") (pin "97") (pinfunction "PE0_97") (pintype "bidirectional"))
    )
    (net (code "93") (name "unconnected-(U1B-PE1-Pad98)") (class "Default")
      (node (ref "U1") (pin "98") (pinfunction "PE1_98") (pintype "bidirectional"))
    )
    (net (code "94") (name "unconnected-(U1B-PE2-Pad1)") (class "Default")
      (node (ref "U1") (pin "1") (pinfunction "PE2_1") (pintype "bidirectional"))
    )
    (net (code "95") (name "unconnected-(U1B-PE3-Pad2)") (class "Default")
      (node (ref "U1") (pin "2") (pinfunction "PE3_2") (pintype "bidirectional"))
    )
    (net (code "96") (name "unconnected-(U1B-PE4-Pad3)") (class "Default")
      (node (ref "U1") (pin "3") (pinfunction "PE4_3") (pintype "bidirectional"))
    )
    (net (code "97") (name "unconnected-(U1B-PE5-Pad4)") (class "Default")
      (node (ref "U1") (pin "4") (pinfunction "PE5_4") (pintype "bidirectional"))
    )
    (net (code "98") (name "unconnected-(U1B-PE6-Pad5)") (class "Default")
      (node (ref "U1") (pin "5") (pinfunction "PE6_5") (pintype "bidirectional"))
    )
  )
)
